# 01_Power_IN.net
KiCad netlist of a schematic drawn in Altium Designer
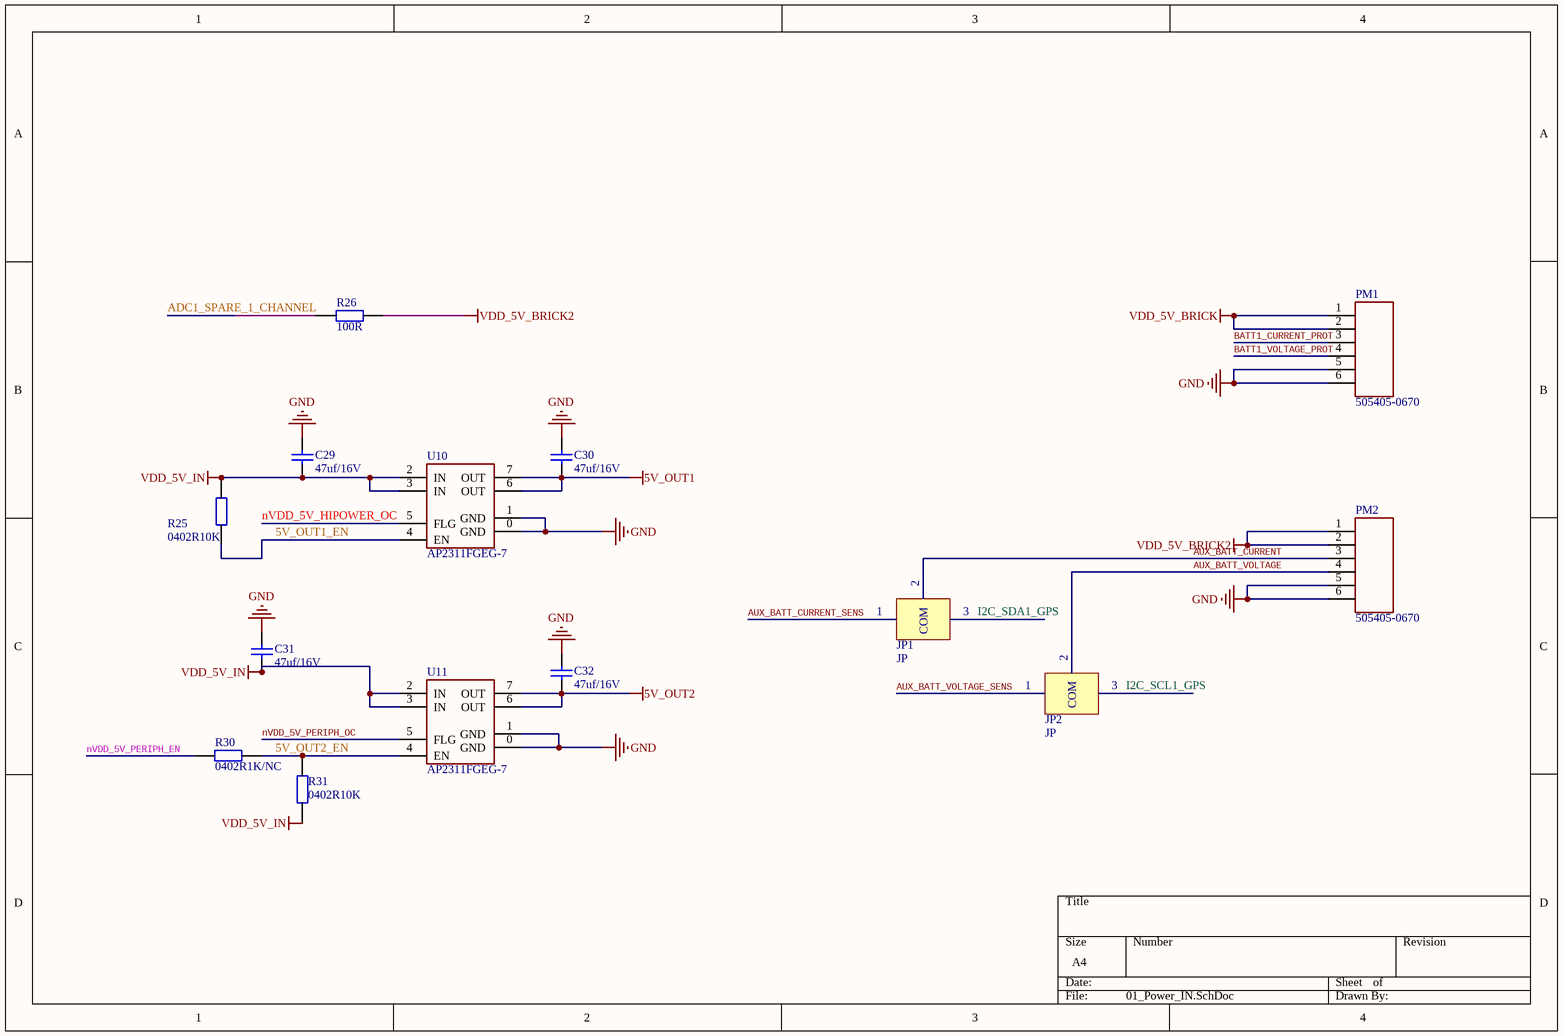
[diagram p0: 01_Power_IN.SchDoc]

(export (version "E")
  (design (tool "Eeschema 10.0.6"))
  (components
    (comp (ref "C29")
      (value "47uf/16V")
      (description "Capacitor")
      (libsource (lib "Miscellaneous Devices") (part "Cap"))
    )
    (comp (ref "C30")
      (value "47uf/16V")
      (description "Capacitor")
      (libsource (lib "Miscellaneous Devices") (part "Cap"))
    )
    (comp (ref "C31")
      (value "47uf/16V")
      (description "Capacitor")
      (libsource (lib "Miscellaneous Devices") (part "Cap"))
    )
    (comp (ref "C32")
      (value "47uf/16V")
      (description "Capacitor")
      (libsource (lib "Miscellaneous Devices") (part "Cap"))
    )
    (comp (ref "JP1") (value "JP") (footprint "0402R-SR") (libsource (lib "CUAV") (part "0402R-SR")))
    (comp (ref "JP2") (value "JP") (footprint "0402R-SR") (libsource (lib "CUAV") (part "0402R-SR")))
    (comp (ref "PM1")
      (value "505405-0670")
      (footprint "5054050660")
      (libsource (lib "CUAV") (part "5054050660"))
    )
    (comp (ref "PM2")
      (value "505405-0670")
      (footprint "5054050660")
      (libsource (lib "CUAV") (part "5054050660"))
    )
    (comp (ref "R25")
      (value "0402R10K")
      (footprint "0402R")
      (description "0402R1K 1%")
      (libsource (lib "") (part "0402R1K_3"))
    )
    (comp (ref "R26")
      (value "100R")
      (footprint "0402R")
      (description "0402R1K 1%")
      (libsource (lib "") (part "0402R1K_2"))
    )
    (comp (ref "R30")
      (value "0402R1K/NC")
      (footprint "0402R")
      (description "0402R1K 1%")
      (libsource (lib "") (part "0402R1K_1"))
    )
    (comp (ref "R31")
      (value "0402R10K")
      (footprint "0402R")
      (description "0402R1K 1%")
      (libsource (lib "CUAV") (part "0402R1K"))
    )
    (comp (ref "U10")
      (value "AP2311FGEG-7")
      (footprint "QFN8_0.65")
      (libsource (lib "CUAV") (part "AP2311FGEG-7"))
    )
    (comp (ref "U11")
      (value "AP2311FGEG-7")
      (footprint "QFN8_0.65")
      (libsource (lib "CUAV") (part "AP2311FGEG-7"))
    )
  )
  (nets
    (net (code "1") (name "/5V_OUT1_EN") (class "Default")
      (node (ref "R25") (pin "1") (pintype "passive"))
      (node (ref "U10") (pin "4") (pinfunction "EN_4") (pintype "passive"))
    )
    (net (code "2") (name "/5V_OUT2_EN") (class "Default")
      (node (ref "R30") (pin "1") (pintype "passive"))
      (node (ref "R31") (pin "1") (pintype "passive"))
      (node (ref "U11") (pin "4") (pinfunction "EN_4") (pintype "passive"))
    )
    (net (code "3") (name "/ADC1_SPARE_1_CHANNEL") (class "Default")
      (node (ref "R26") (pin "1") (pintype "passive"))
    )
    (net (code "4") (name "/AUX_BATT_CURRENT") (class "Default")
      (node (ref "JP1") (pin "2") (pinfunction "COM_2") (pintype "passive"))
      (node (ref "PM2") (pin "3") (pintype "passive"))
    )
    (net (code "5") (name "/AUX_BATT_CURRENT_SENS") (class "Default")
      (node (ref "JP1") (pin "1") (pintype "passive"))
    )
    (net (code "6") (name "/AUX_BATT_VOLTAGE") (class "Default")
      (node (ref "JP2") (pin "2") (pinfunction "COM_2") (pintype "passive"))
      (node (ref "PM2") (pin "4") (pintype "passive"))
    )
    (net (code "7") (name "/AUX_BATT_VOLTAGE_SENS") (class "Default")
      (node (ref "JP2") (pin "1") (pintype "passive"))
    )
    (net (code "8") (name "/BATT1_CURRENT_PROT") (class "Default")
      (node (ref "PM1") (pin "3") (pintype "passive"))
    )
    (net (code "9") (name "/BATT1_VOLTAGE_PROT") (class "Default")
      (node (ref "PM1") (pin "4") (pintype "passive"))
    )
    (net (code "10") (name "/I2C_SCL1_GPS") (class "Default")
      (node (ref "JP2") (pin "3") (pintype "passive"))
    )
    (net (code "11") (name "/I2C_SDA1_GPS") (class "Default")
      (node (ref "JP1") (pin "3") (pintype "passive"))
    )
    (net (code "12") (name "/nVDD_5V_HIPOWER_OC") (class "Default")
      (node (ref "U10") (pin "5") (pinfunction "FLG_5") (pintype "passive"))
    )
    (net (code "13") (name "/nVDD_5V_PERIPH_EN") (class "Default")
      (node (ref "R30") (pin "2") (pintype "passive"))
    )
    (net (code "14") (name "/nVDD_5V_PERIPH_OC") (class "Default")
      (node (ref "U11") (pin "5") (pinfunction "FLG_5") (pintype "passive"))
    )
    (net (code "15") (name "5V_OUT1") (class "Default")
      (node (ref "C30") (pin "1") (pinfunction "1_1") (pintype "passive"))
      (node (ref "U10") (pin "6") (pinfunction "OUT_6") (pintype "passive"))
      (node (ref "U10") (pin "7") (pinfunction "OUT_7") (pintype "passive"))
    )
    (net (code "16") (name "5V_OUT2") (class "Default")
      (node (ref "C32") (pin "1") (pinfunction "1_1") (pintype "passive"))
      (node (ref "U11") (pin "6") (pinfunction "OUT_6") (pintype "passive"))
      (node (ref "U11") (pin "7") (pinfunction "OUT_7") (pintype "passive"))
    )
    (net (code "17") (name "GND") (class "Default")
      (node (ref "C29") (pin "2") (pinfunction "2_2") (pintype "passive"))
      (node (ref "C30") (pin "2") (pinfunction "2_2") (pintype "passive"))
      (node (ref "C31") (pin "2") (pinfunction "2_2") (pintype "passive"))
      (node (ref "C32") (pin "2") (pinfunction "2_2") (pintype "passive"))
      (node (ref "PM1") (pin "5") (pintype "passive"))
      (node (ref "PM1") (pin "6") (pintype "passive"))
      (node (ref "PM2") (pin "5") (pintype "passive"))
      (node (ref "PM2") (pin "6") (pintype "passive"))
      (node (ref "U10") (pin "0") (pinfunction "GND_0") (pintype "passive"))
      (node (ref "U10") (pin "1") (pinfunction "GND_1") (pintype "passive"))
      (node (ref "U11") (pin "0") (pinfunction "GND_0") (pintype "passive"))
      (node (ref "U11") (pin "1") (pinfunction "GND_1") (pintype "passive"))
    )
    (net (code "18") (name "VDD_5V_BRICK") (class "Default")
      (node (ref "PM1") (pin "1") (pintype "passive"))
      (node (ref "PM1") (pin "2") (pintype "passive"))
    )
    (net (code "19") (name "VDD_5V_BRICK2") (class "Default")
      (node (ref "PM2") (pin "1") (pintype "passive"))
      (node (ref "PM2") (pin "2") (pintype "passive"))
      (node (ref "R26") (pin "2") (pintype "passive"))
    )
    (net (code "20") (name "VDD_5V_IN") (class "Default")
      (node (ref "C29") (pin "1") (pinfunction "1_1") (pintype "passive"))
      (node (ref "C31") (pin "1") (pinfunction "1_1") (pintype "passive"))
      (node (ref "R25") (pin "2") (pintype "passive"))
      (node (ref "R31") (pin "2") (pintype "passive"))
      (node (ref "U10") (pin "2") (pinfunction "IN_2") (pintype "passive"))
      (node (ref "U10") (pin "3") (pinfunction "IN_3") (pintype "passive"))
      (node (ref "U11") (pin "2") (pinfunction "IN_2") (pintype "passive"))
      (node (ref "U11") (pin "3") (pinfunction "IN_3") (pintype "passive"))
    )
  )
)
